# Vanta-Black_v3.net
KiCad netlist of a schematic drawn in EAGLE
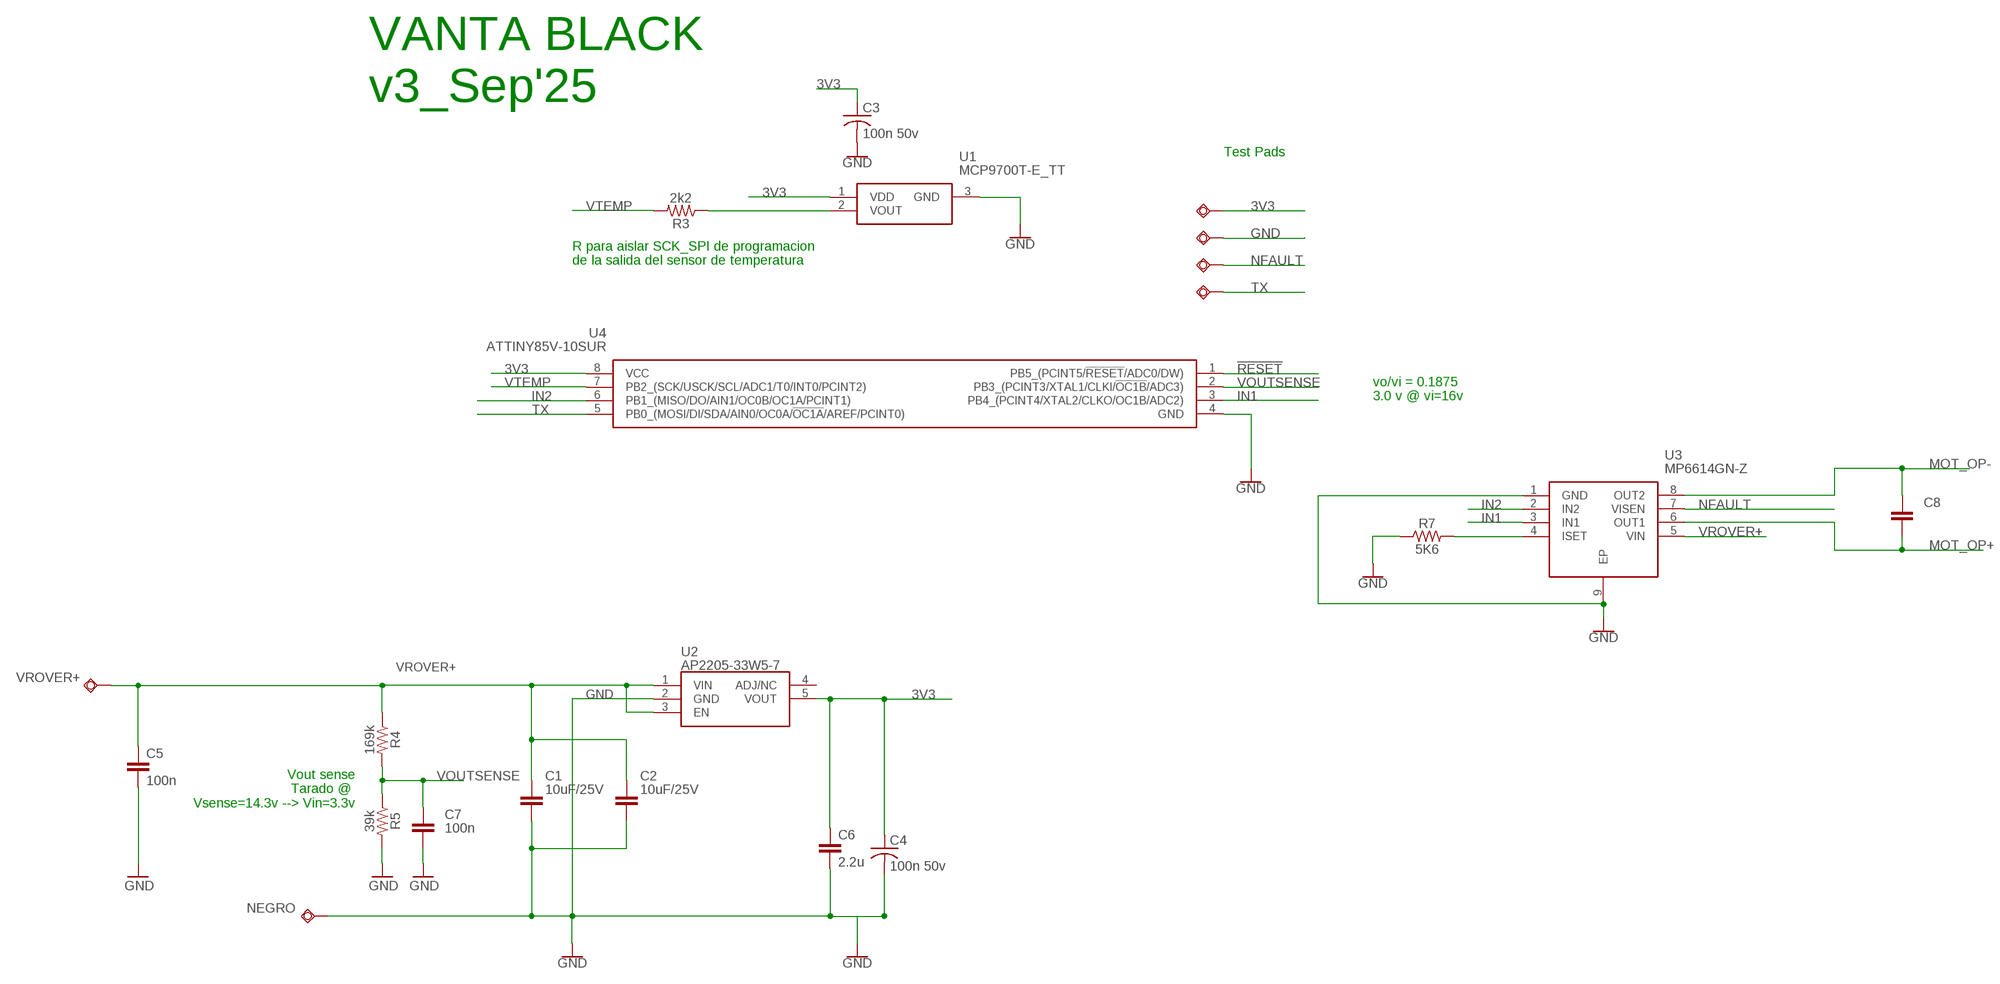
[diagram p0: schematic, sheet 1]

(export (version "E")
  (design (tool "Eeschema 10.0.6"))
  (components
    (comp (ref "3V3")
      (value "TESTPAD_TPSQB1,27")
      (footprint "eagle-import:TESTPAD_B1,27")
      (libsource (lib "eagle-import") (part "TESTPAD_TPSQB1,27"))
    )
    (comp (ref "C1")
      (value "10uF/25V")
      (footprint "eagle-import:CAPC2012X110")
      (libsource (lib "eagle-import") (part "CCHIP-0805(2012-METRIC)_"))
    )
    (comp (ref "C2")
      (value "10uF/25V")
      (footprint "eagle-import:CAPC2012X110")
      (libsource (lib "eagle-import") (part "CCHIP-0805(2012-METRIC)_"))
    )
    (comp (ref "C3")
      (value "100n 50v")
      (footprint "eagle-import:C0805")
      (libsource (lib "eagle-import") (part "C-USC0805"))
    )
    (comp (ref "C4")
      (value "100n 50v")
      (footprint "eagle-import:C0805")
      (libsource (lib "eagle-import") (part "C-USC0805"))
    )
    (comp (ref "C5")
      (value "100n")
      (footprint "eagle-import:0603-CAP")
      (libsource (lib "eagle-import") (part "4.7UF-6.3V-10%(0603)0603"))
    )
    (comp (ref "C6")
      (value "2.2u")
      (footprint "eagle-import:0603-CAP")
      (libsource (lib "eagle-import") (part "4.7UF-6.3V-10%(0603)0603"))
    )
    (comp (ref "C7")
      (value "100n")
      (footprint "eagle-import:0603")
      (libsource (lib "eagle-import") (part "0.1UF-0603-25V-(+80/-20%)"))
    )
    (comp (ref "C8")
      (value "100n")
      (footprint "eagle-import:0805")
      (libsource (lib "eagle-import") (part "CAP0805"))
    )
    (comp (ref "GND")
      (value "TESTPAD_TPSQB1,27")
      (footprint "eagle-import:TESTPAD_B1,27")
      (libsource (lib "eagle-import") (part "TESTPAD_TPSQB1,27"))
    )
    (comp (ref "NEGRO")
      (value "TESTPAD_TPSQTP10SQ")
      (footprint "eagle-import:TESTPAD_TP10SQ")
      (libsource (lib "eagle-import") (part "BeagleBone_Blue_R3_5828899_TESTPAD_TPSQTP10SQ"))
    )
    (comp (ref "R3")
      (value "2k2")
      (footprint "eagle-import:0603")
      (libsource (lib "eagle-import") (part "RESISTOR0603"))
    )
    (comp (ref "R4")
      (value "169k")
      (footprint "eagle-import:0603")
      (libsource (lib "eagle-import") (part "RESISTOR0603"))
    )
    (comp (ref "R5")
      (value "39k")
      (footprint "eagle-import:0603")
      (libsource (lib "eagle-import") (part "RESISTOR0603"))
    )
    (comp (ref "R7")
      (value "5K6")
      (footprint "eagle-import:0603")
      (libsource (lib "eagle-import") (part "RESISTOR0603"))
    )
    (comp (ref "TX")
      (value "TESTPAD_TPSQB1,27")
      (footprint "eagle-import:TESTPAD_B1,27")
      (libsource (lib "eagle-import") (part "TESTPAD_TPSQB1,27"))
    )
    (comp (ref "U1")
      (value "MCP9700T-E_TT")
      (footprint "eagle-import:SOT95P237X112-3N")
      (fields
        (field (name "ARROW_PART_NUMBER") "MCP9700T-E/TT")
        (field (name "MOUSER_PART_NUMBER") "579-MCP9700T-E/TT")
      )
      (libsource (lib "eagle-import") (part "MCP9700T-E_TT"))
    )
    (comp (ref "U2")
      (value "AP2205-33W5-7")
      (footprint "eagle-import:SOT95P282X145-5N")
      (fields
        (field (name "MANUFACTURER_PART_NUMBER") "AP2205-W5-7")
        (field (name "MOUSER_PART_NUMBER") "621-AP2205-W5-7")
      )
      (libsource (lib "eagle-import") (part "AP2205-W5-7"))
    )
    (comp (ref "U3")
      (value "MP6614GN-Z")
      (footprint "eagle-import:SOIC127P600X170-9N")
      (fields (field (name "MOUSER_PART_NUMBER") "946-MP6614GN-Z"))
      (libsource (lib "eagle-import") (part "MP6614GN-Z"))
    )
    (comp (ref "U4")
      (value "ATTINY85V-10SUR")
      (footprint "eagle-import:SOIC127P798X216-8N")
      (fields (field (name "FARNELL2_PART_NUMBER") "2851618RL"))
      (libsource (lib "eagle-import") (part "ATTINY85V-10SUR"))
    )
    (comp (ref "VISEN")
      (value "TESTPAD_TPSQB1,27")
      (footprint "eagle-import:TESTPAD_B1,27")
      (libsource (lib "eagle-import") (part "TESTPAD_TPSQB1,27"))
    )
    (comp (ref "VROVER+")
      (value "TESTPAD_TPSQTP10SQ")
      (footprint "eagle-import:TESTPAD_TP10SQ")
      (libsource (lib "eagle-import") (part "BeagleBone_Blue_R3_5828899_TESTPAD_TPSQTP10SQ"))
    )
  )
  (nets
    (net (code "1") (name "/3V3") (class "Default")
      (node (ref "3V3") (pin "TP") (pinfunction "TP_TP") (pintype "input"))
      (node (ref "C3") (pin "1") (pinfunction "1_1") (pintype "passive"))
      (node (ref "C4") (pin "1") (pinfunction "1_1") (pintype "passive"))
      (node (ref "C6") (pin "1") (pinfunction "1_1") (pintype "passive"))
      (node (ref "U1") (pin "1") (pinfunction "VDD_1") (pintype "bidirectional"))
      (node (ref "U2") (pin "5") (pinfunction "VOUT_5") (pintype "bidirectional"))
      (node (ref "U4") (pin "8") (pinfunction "VCC_8") (pintype "bidirectional"))
    )
    (net (code "2") (name "/IN1") (class "Default")
      (node (ref "U3") (pin "3") (pinfunction "IN1_3") (pintype "bidirectional"))
      (node (ref "U4") (pin "3") (pinfunction "PB4_(PCINT4/XTAL2/CLKO/OC1B/ADC2)_3") (pintype "bidirectional"))
    )
    (net (code "3") (name "/IN2") (class "Default")
      (node (ref "U3") (pin "2") (pinfunction "IN2_2") (pintype "bidirectional"))
      (node (ref "U4") (pin "6") (pinfunction "PB1_(MISO/DO/AIN1/OC0B/OC1A/PCINT1)_6") (pintype "bidirectional"))
    )
    (net (code "4") (name "/MOT_OP+") (class "Default")
      (node (ref "C8") (pin "2") (pinfunction "2_2") (pintype "passive"))
      (node (ref "U3") (pin "6") (pinfunction "OUT1_6") (pintype "bidirectional"))
    )
    (net (code "5") (name "/MOT_OP-") (class "Default")
      (node (ref "C8") (pin "1") (pinfunction "1_1") (pintype "passive"))
      (node (ref "U3") (pin "8") (pinfunction "OUT2_8") (pintype "bidirectional"))
    )
    (net (code "6") (name "/NFAULT") (class "Default")
      (node (ref "U3") (pin "7") (pinfunction "VISEN_7") (pintype "bidirectional"))
      (node (ref "VISEN") (pin "TP") (pinfunction "TP_TP") (pintype "input"))
    )
    (net (code "7") (name "/TX") (class "Default")
      (node (ref "TX") (pin "TP") (pinfunction "TP_TP") (pintype "input"))
      (node (ref "U4") (pin "5") (pinfunction "PB0_(MOSI/DI/SDA/AIN0/OC0A/~{OC1A}/AREF/PCINT0)_5") (pintype "bidirectional"))
    )
    (net (code "8") (name "/VOUTSENSE") (class "Default")
      (node (ref "C7") (pin "1") (pinfunction "1_1") (pintype "passive"))
      (node (ref "R4") (pin "2") (pinfunction "2_2") (pintype "passive"))
      (node (ref "R5") (pin "1") (pinfunction "1_1") (pintype "passive"))
      (node (ref "U4") (pin "2") (pinfunction "PB3_(PCINT3/XTAL1/CLKI/~{OC1B}/ADC3)_2") (pintype "bidirectional"))
    )
    (net (code "9") (name "/VROVER+") (class "Default")
      (node (ref "C1") (pin "1") (pinfunction "1_1") (pintype "passive"))
      (node (ref "C2") (pin "1") (pinfunction "1_1") (pintype "passive"))
      (node (ref "C5") (pin "1") (pinfunction "1_1") (pintype "passive"))
      (node (ref "R4") (pin "1") (pinfunction "1_1") (pintype "passive"))
      (node (ref "U2") (pin "1") (pinfunction "VIN_1") (pintype "bidirectional"))
      (node (ref "U2") (pin "3") (pinfunction "EN_3") (pintype "bidirectional"))
      (node (ref "U3") (pin "5") (pinfunction "VIN_5") (pintype "bidirectional"))
      (node (ref "VROVER+") (pin "TP") (pinfunction "TP_TP") (pintype "input"))
    )
    (net (code "10") (name "/VTEMP") (class "Default")
      (node (ref "R3") (pin "2") (pinfunction "2_2") (pintype "passive"))
      (node (ref "U4") (pin "7") (pinfunction "PB2_(SCK/USCK/SCL/ADC1/T0/INT0/PCINT2)_7") (pintype "bidirectional"))
    )
    (net (code "11") (name "/~{RESET}") (class "Default")
      (node (ref "U4") (pin "1") (pinfunction "PB5_(PCINT5/~{RESET}/ADC0/DW)_1") (pintype "bidirectional"))
    )
    (net (code "12") (name "GND") (class "Default")
      (node (ref "C1") (pin "2") (pinfunction "2_2") (pintype "passive"))
      (node (ref "C2") (pin "2") (pinfunction "2_2") (pintype "passive"))
      (node (ref "C3") (pin "2") (pinfunction "2_2") (pintype "passive"))
      (node (ref "C4") (pin "2") (pinfunction "2_2") (pintype "passive"))
      (node (ref "C5") (pin "2") (pinfunction "2_2") (pintype "passive"))
      (node (ref "C6") (pin "2") (pinfunction "2_2") (pintype "passive"))
      (node (ref "C7") (pin "2") (pinfunction "2_2") (pintype "passive"))
      (node (ref "GND") (pin "TP") (pinfunction "TP_TP") (pintype "input"))
      (node (ref "NEGRO") (pin "TP") (pinfunction "TP_TP") (pintype "input"))
      (node (ref "R5") (pin "2") (pinfunction "2_2") (pintype "passive"))
      (node (ref "R7") (pin "1") (pinfunction "1_1") (pintype "passive"))
      (node (ref "U1") (pin "3") (pinfunction "GND_3") (pintype "bidirectional"))
      (node (ref "U2") (pin "2") (pinfunction "GND_2") (pintype "bidirectional"))
      (node (ref "U3") (pin "1") (pinfunction "GND_1") (pintype "bidirectional"))
      (node (ref "U3") (pin "9") (pinfunction "EP_9") (pintype "bidirectional"))
      (node (ref "U4") (pin "4") (pinfunction "GND_4") (pintype "bidirectional"))
    )
    (net (code "13") (name "Net-(U1-VOUT)") (class "Default")
      (node (ref "R3") (pin "1") (pinfunction "1_1") (pintype "passive"))
      (node (ref "U1") (pin "2") (pinfunction "VOUT_2") (pintype "bidirectional"))
    )
    (net (code "14") (name "Net-(U3-ISET)") (class "Default")
      (node (ref "R7") (pin "2") (pinfunction "2_2") (pintype "passive"))
      (node (ref "U3") (pin "4") (pinfunction "ISET_4") (pintype "bidirectional"))
    )
    (net (code "15") (name "unconnected-(U2-ADJ{slash}NC-Pad4)") (class "Default")
      (node (ref "U2") (pin "4") (pinfunction "ADJ/NC_4") (pintype "bidirectional"))
    )
  )
)
